# gain_setting.net
KiCad netlist of a schematic drawn in Altium Designer
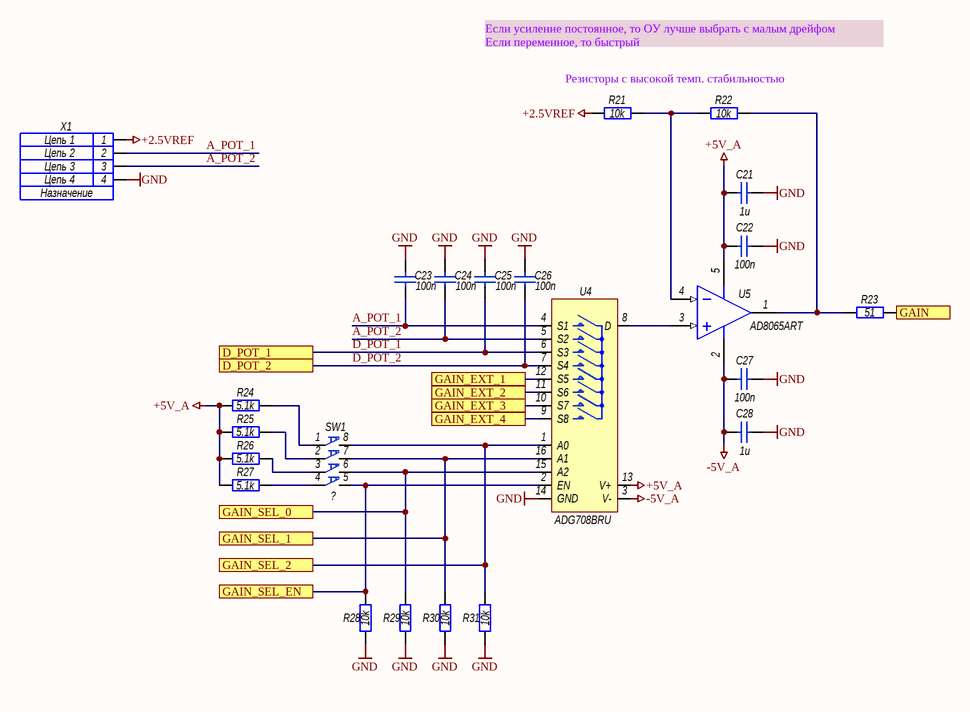
[diagram p0: gain_setting.SchDoc]

(export (version "E")
  (design (tool "Eeschema 10.0.6"))
  (components
    (comp (ref "C21")
      (value "1u")
      (footprint "CAP_0603")
      (description "Конденсатор")
      (libsource (lib "SCH_LIB") (part "Capacitor"))
    )
    (comp (ref "C22")
      (value "100n")
      (footprint "CAP_0603")
      (description "Конденсатор")
      (libsource (lib "SCH_LIB") (part "Capacitor"))
    )
    (comp (ref "C23")
      (value "100n")
      (footprint "CAP_0603")
      (description "Конденсатор")
      (libsource (lib "SCH_LIB") (part "Capacitor"))
    )
    (comp (ref "C24")
      (value "100n")
      (footprint "CAP_0603")
      (description "Конденсатор")
      (libsource (lib "SCH_LIB") (part "Capacitor"))
    )
    (comp (ref "C25")
      (value "100n")
      (footprint "CAP_0603")
      (description "Конденсатор")
      (libsource (lib "SCH_LIB") (part "Capacitor"))
    )
    (comp (ref "C26")
      (value "100n")
      (footprint "CAP_0603")
      (description "Конденсатор")
      (libsource (lib "SCH_LIB") (part "Capacitor"))
    )
    (comp (ref "C27")
      (value "100n")
      (footprint "CAP_0603")
      (description "Конденсатор")
      (libsource (lib "SCH_LIB") (part "Capacitor"))
    )
    (comp (ref "C28")
      (value "1u")
      (footprint "CAP_0603")
      (description "Конденсатор")
      (libsource (lib "SCH_LIB") (part "Capacitor"))
    )
    (comp (ref "R21")
      (value "10k")
      (footprint "RES_0603")
      (description "Резистор")
      (libsource (lib "SCH_LIB") (part "Resisitor"))
    )
    (comp (ref "R22")
      (value "10k")
      (footprint "RES_0603")
      (description "Резистор")
      (libsource (lib "SCH_LIB") (part "Resisitor"))
    )
    (comp (ref "R23")
      (value "51")
      (footprint "RES_0603")
      (description "Резистор")
      (libsource (lib "SCH_LIB") (part "Resisitor"))
    )
    (comp (ref "R24")
      (value "5.1k")
      (footprint "RES_0603")
      (description "Резистор")
      (libsource (lib "SCH_LIB") (part "Resisitor"))
    )
    (comp (ref "R25")
      (value "5.1k")
      (footprint "RES_0603")
      (description "Резистор")
      (libsource (lib "SCH_LIB") (part "Resisitor"))
    )
    (comp (ref "R26")
      (value "5.1k")
      (footprint "RES_0603")
      (description "Резистор")
      (libsource (lib "SCH_LIB") (part "Resisitor"))
    )
    (comp (ref "R27")
      (value "5.1k")
      (footprint "RES_0603")
      (description "Резистор")
      (libsource (lib "SCH_LIB") (part "Resisitor"))
    )
    (comp (ref "R28")
      (value "10k")
      (footprint "RES_0603")
      (description "Резистор")
      (libsource (lib "SCH_LIB") (part "Resisitor"))
    )
    (comp (ref "R29")
      (value "10k")
      (footprint "RES_0603")
      (description "Резистор")
      (libsource (lib "SCH_LIB") (part "Resisitor"))
    )
    (comp (ref "R30")
      (value "10k")
      (footprint "RES_0603")
      (description "Резистор")
      (libsource (lib "SCH_LIB") (part "Resisitor"))
    )
    (comp (ref "R31")
      (value "10k")
      (footprint "RES_0603")
      (description "Резистор")
      (libsource (lib "SCH_LIB") (part "Resisitor"))
    )
    (comp (ref "SW1")
      (value "?")
      (footprint "SWD3-4")
      (description "Переключатель 4 группы (под углом)\r\nDS1040-04R;\r\nSWD3-4;\r\nL-KLS7-DP-04-B-00;")
      (libsource (lib "SCH_LIB") (part "SWD3-4"))
    )
    (comp (ref "U4")
      (value "ADG708BRU")
      (footprint "tssop16")
      (libsource (lib "SCH_LIB") (part "MUX 1{colon}8 TSSOP16"))
    )
    (comp (ref "U5")
      (value "AD8065ART")
      (footprint "sot235")
      (description "Операционный усилитель")
      (libsource (lib "SCH_LIB") (part "OPAMP SOT235"))
    )
    (comp (ref "X1")
      (value "Model")
      (footprint "PLS-4-3D")
      (fields
        (field (name "NET4") "Цепь 4")
        (field (name "NET1") "Цепь 1")
        (field (name "NET2") "Цепь 2")
        (field (name "NAME") "Назначение")
        (field (name "NET3") "Цепь 3")
      )
      (libsource (lib "SCH_LIB") (part "Connector 4"))
    )
  )
  (nets
    (net (code "1") (name "+2.5VREF") (class "Default")
      (node (ref "R21") (pin "1") (pinfunction "1_1") (pintype "passive"))
      (node (ref "X1") (pin "1") (pinfunction "1_1") (pintype "passive"))
    )
    (net (code "2") (name "+5V_A") (class "Default")
      (node (ref "C21") (pin "1") (pinfunction "1_1") (pintype "passive"))
      (node (ref "C22") (pin "1") (pinfunction "1_1") (pintype "passive"))
      (node (ref "R24") (pin "1") (pinfunction "1_1") (pintype "passive"))
      (node (ref "R25") (pin "1") (pinfunction "1_1") (pintype "passive"))
      (node (ref "R26") (pin "1") (pinfunction "1_1") (pintype "passive"))
      (node (ref "R27") (pin "1") (pinfunction "1_1") (pintype "passive"))
      (node (ref "U4") (pin "13") (pinfunction "V+_13") (pintype "passive"))
      (node (ref "U5") (pin "5") (pinfunction "V+_5") (pintype "power_in"))
    )
    (net (code "3") (name "-5V_A") (class "Default")
      (node (ref "C27") (pin "1") (pinfunction "1_1") (pintype "passive"))
      (node (ref "C28") (pin "1") (pinfunction "1_1") (pintype "passive"))
      (node (ref "U4") (pin "3") (pinfunction "V-_3") (pintype "passive"))
      (node (ref "U5") (pin "2") (pinfunction "V-_2") (pintype "power_in"))
    )
    (net (code "4") (name "/A_POT_1") (class "Default")
      (node (ref "C23") (pin "1") (pinfunction "1_1") (pintype "passive"))
      (node (ref "U4") (pin "4") (pinfunction "S1_4") (pintype "passive"))
      (node (ref "X1") (pin "2") (pinfunction "2_2") (pintype "passive"))
    )
    (net (code "5") (name "/A_POT_2") (class "Default")
      (node (ref "C24") (pin "1") (pinfunction "1_1") (pintype "passive"))
      (node (ref "U4") (pin "5") (pinfunction "S2_5") (pintype "passive"))
      (node (ref "X1") (pin "3") (pinfunction "3_3") (pintype "passive"))
    )
    (net (code "6") (name "/D_POT_1") (class "Default")
      (node (ref "C25") (pin "1") (pinfunction "1_1") (pintype "passive"))
      (node (ref "U4") (pin "6") (pinfunction "S3_6") (pintype "passive"))
    )
    (net (code "7") (name "/D_POT_2") (class "Default")
      (node (ref "C26") (pin "1") (pinfunction "1_1") (pintype "passive"))
      (node (ref "U4") (pin "7") (pinfunction "S4_7") (pintype "passive"))
    )
    (net (code "8") (name "/GAIN") (class "Default")
      (node (ref "R23") (pin "2") (pinfunction "2_2") (pintype "passive"))
    )
    (net (code "9") (name "/GAIN_EXT_1") (class "Default")
      (node (ref "U4") (pin "12") (pinfunction "S5_12") (pintype "passive"))
    )
    (net (code "10") (name "/GAIN_EXT_2") (class "Default")
      (node (ref "U4") (pin "11") (pinfunction "S6_11") (pintype "passive"))
    )
    (net (code "11") (name "/GAIN_EXT_3") (class "Default")
      (node (ref "U4") (pin "10") (pinfunction "S7_10") (pintype "passive"))
    )
    (net (code "12") (name "/GAIN_EXT_4") (class "Default")
      (node (ref "U4") (pin "9") (pinfunction "S8_9") (pintype "passive"))
    )
    (net (code "13") (name "/GAIN_SEL_0") (class "Default")
      (node (ref "R29") (pin "2") (pinfunction "2_2") (pintype "passive"))
      (node (ref "SW1") (pin "6") (pintype "passive"))
      (node (ref "U4") (pin "15") (pinfunction "A2_15") (pintype "passive"))
    )
    (net (code "14") (name "/GAIN_SEL_1") (class "Default")
      (node (ref "R30") (pin "2") (pinfunction "2_2") (pintype "passive"))
      (node (ref "SW1") (pin "7") (pintype "passive"))
      (node (ref "U4") (pin "16") (pinfunction "A1_16") (pintype "passive"))
    )
    (net (code "15") (name "/GAIN_SEL_2") (class "Default")
      (node (ref "R31") (pin "2") (pinfunction "2_2") (pintype "passive"))
      (node (ref "SW1") (pin "8") (pintype "passive"))
      (node (ref "U4") (pin "1") (pinfunction "A0_1") (pintype "passive"))
    )
    (net (code "16") (name "/GAIN_SEL_EN") (class "Default")
      (node (ref "R28") (pin "2") (pinfunction "2_2") (pintype "passive"))
      (node (ref "SW1") (pin "5") (pintype "passive"))
      (node (ref "U4") (pin "2") (pinfunction "EN_2") (pintype "passive"))
    )
    (net (code "17") (name "GND") (class "Default")
      (node (ref "C21") (pin "2") (pinfunction "2_2") (pintype "passive"))
      (node (ref "C22") (pin "2") (pinfunction "2_2") (pintype "passive"))
      (node (ref "C23") (pin "2") (pinfunction "2_2") (pintype "passive"))
      (node (ref "C24") (pin "2") (pinfunction "2_2") (pintype "passive"))
      (node (ref "C25") (pin "2") (pinfunction "2_2") (pintype "passive"))
      (node (ref "C26") (pin "2") (pinfunction "2_2") (pintype "passive"))
      (node (ref "C27") (pin "2") (pinfunction "2_2") (pintype "passive"))
      (node (ref "C28") (pin "2") (pinfunction "2_2") (pintype "passive"))
      (node (ref "R28") (pin "1") (pinfunction "1_1") (pintype "passive"))
      (node (ref "R29") (pin "1") (pinfunction "1_1") (pintype "passive"))
      (node (ref "R30") (pin "1") (pinfunction "1_1") (pintype "passive"))
      (node (ref "R31") (pin "1") (pinfunction "1_1") (pintype "passive"))
      (node (ref "U4") (pin "14") (pinfunction "GND_14") (pintype "passive"))
      (node (ref "X1") (pin "4") (pinfunction "4_4") (pintype "passive"))
    )
    (net (code "18") (name "Net-(R24-Pad2)") (class "Default")
      (node (ref "R24") (pin "2") (pinfunction "2_2") (pintype "passive"))
      (node (ref "SW1") (pin "1") (pintype "passive"))
    )
    (net (code "19") (name "Net-(R25-Pad2)") (class "Default")
      (node (ref "R25") (pin "2") (pinfunction "2_2") (pintype "passive"))
      (node (ref "SW1") (pin "2") (pintype "passive"))
    )
    (net (code "20") (name "Net-(R26-Pad2)") (class "Default")
      (node (ref "R26") (pin "2") (pinfunction "2_2") (pintype "passive"))
      (node (ref "SW1") (pin "3") (pintype "passive"))
    )
    (net (code "21") (name "Net-(R27-Pad2)") (class "Default")
      (node (ref "R27") (pin "2") (pinfunction "2_2") (pintype "passive"))
      (node (ref "SW1") (pin "4") (pintype "passive"))
    )
    (net (code "22") (name "Net-(U4-D)") (class "Default")
      (node (ref "U4") (pin "8") (pinfunction "D_8") (pintype "passive"))
      (node (ref "U5") (pin "3") (pinfunction "IN+_3") (pintype "input"))
    )
    (net (code "23") (name "Net-(U5-IN-)") (class "Default")
      (node (ref "R21") (pin "2") (pinfunction "2_2") (pintype "passive"))
      (node (ref "R22") (pin "1") (pinfunction "1_1") (pintype "passive"))
      (node (ref "U5") (pin "4") (pinfunction "IN-_4") (pintype "input"))
    )
    (net (code "24") (name "Net-(U5-OUT)") (class "Default")
      (node (ref "R22") (pin "2") (pinfunction "2_2") (pintype "passive"))
      (node (ref "R23") (pin "1") (pinfunction "1_1") (pintype "passive"))
      (node (ref "U5") (pin "1") (pinfunction "OUT_1") (pintype "open_collector"))
    )
  )
)
